# MicroMod-Teensy.net
KiCad netlist of a schematic drawn in EAGLE
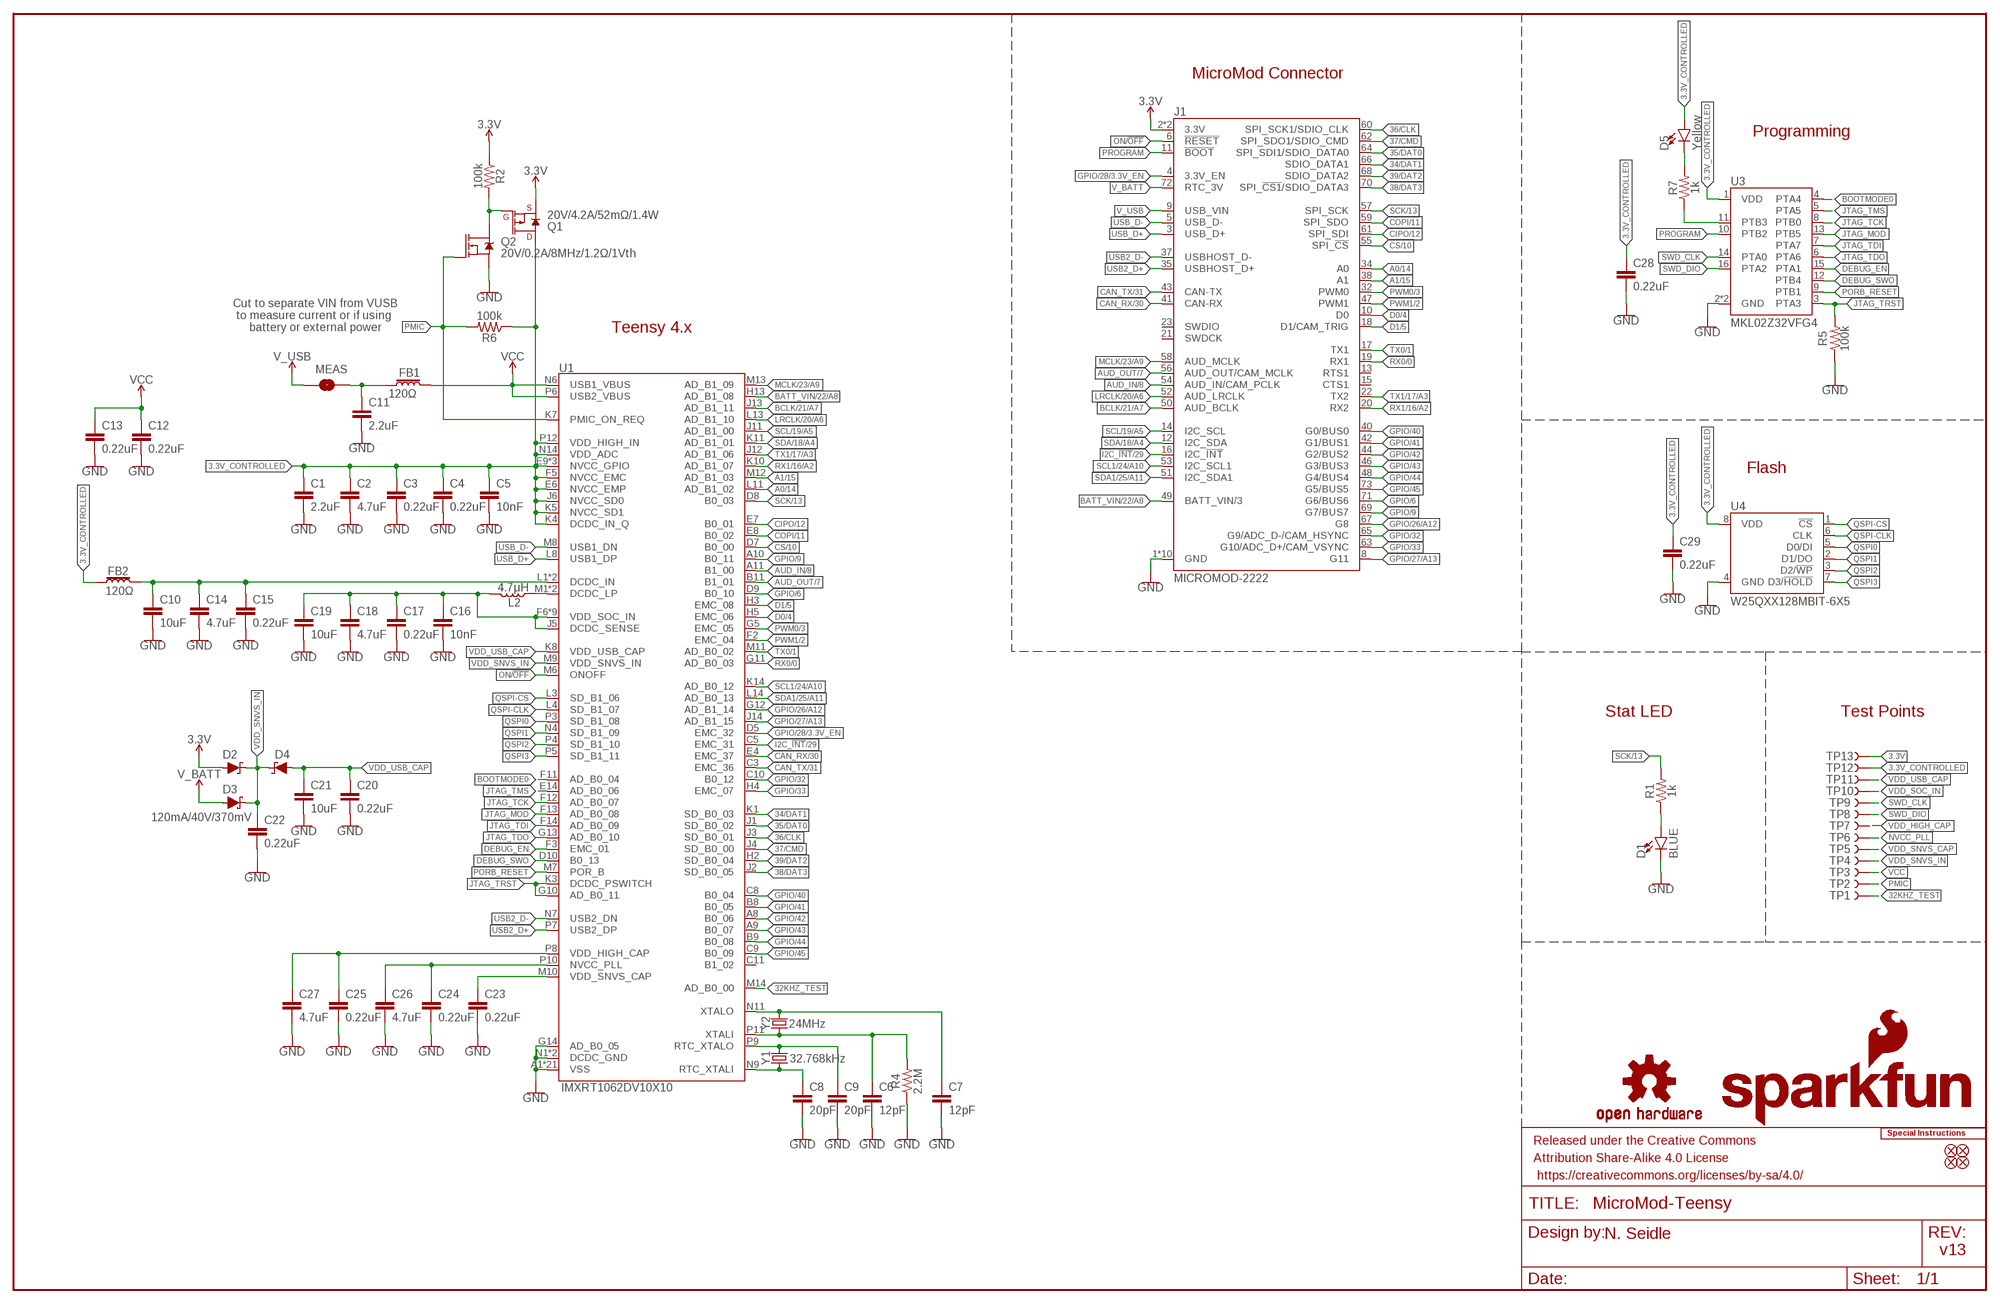
[diagram p0: schematic, sheet 1]

(export (version "E")
  (design (tool "Eeschema 10.0.6"))
  (components
    (comp (ref "C1")
      (value "2.2uF")
      (footprint "eagle-import:0402-TIGHT")
      (libsource (lib "eagle-import") (part "2.2UF-0402_TIGHT-10V-10%-X5R"))
    )
    (comp (ref "C2")
      (value "4.7uF")
      (footprint "eagle-import:0402-TIGHT")
      (libsource (lib "eagle-import") (part "4.7UF-0402_TIGHT-6.3V-20%-X5R"))
    )
    (comp (ref "C3")
      (value "0.22uF")
      (footprint "eagle-import:0402-TIGHT")
      (libsource (lib "eagle-import") (part "0.22UF-0402T-10V-10%"))
    )
    (comp (ref "C4")
      (value "0.22uF")
      (footprint "eagle-import:0402-TIGHT")
      (libsource (lib "eagle-import") (part "0.22UF-0402T-10V-10%"))
    )
    (comp (ref "C5")
      (value "10nF")
      (footprint "eagle-import:0402-TIGHT")
      (libsource (lib "eagle-import") (part "10NF-0402T-25V-10%"))
    )
    (comp (ref "C6")
      (value "12pF")
      (footprint "eagle-import:0402-TIGHT")
      (libsource (lib "eagle-import") (part "12PF-0402T-50V-5%"))
    )
    (comp (ref "C7")
      (value "12pF")
      (footprint "eagle-import:0402-TIGHT")
      (libsource (lib "eagle-import") (part "12PF-0402T-50V-5%"))
    )
    (comp (ref "C8")
      (value "20pF")
      (footprint "eagle-import:0402-TIGHT")
      (libsource (lib "eagle-import") (part "20PF-0402T-50V-5%"))
    )
    (comp (ref "C9")
      (value "20pF")
      (footprint "eagle-import:0402-TIGHT")
      (libsource (lib "eagle-import") (part "20PF-0402T-50V-5%"))
    )
    (comp (ref "C10")
      (value "10uF")
      (footprint "eagle-import:0402-TIGHT")
      (libsource (lib "eagle-import") (part "10UF-0402T-6.3V-20%"))
    )
    (comp (ref "C11")
      (value "2.2uF")
      (footprint "eagle-import:0402-TIGHT")
      (libsource (lib "eagle-import") (part "2.2UF-0402_TIGHT-10V-10%-X5R"))
    )
    (comp (ref "C12")
      (value "0.22uF")
      (footprint "eagle-import:0402-TIGHT")
      (libsource (lib "eagle-import") (part "0.22UF-0402T-10V-10%"))
    )
    (comp (ref "C13")
      (value "0.22uF")
      (footprint "eagle-import:0402-TIGHT")
      (libsource (lib "eagle-import") (part "0.22UF-0402T-10V-10%"))
    )
    (comp (ref "C14")
      (value "4.7uF")
      (footprint "eagle-import:0402-TIGHT")
      (libsource (lib "eagle-import") (part "4.7UF-0402_TIGHT-6.3V-20%-X5R"))
    )
    (comp (ref "C15")
      (value "0.22uF")
      (footprint "eagle-import:0402-TIGHT")
      (libsource (lib "eagle-import") (part "0.22UF-0402T-10V-10%"))
    )
    (comp (ref "C16")
      (value "10nF")
      (footprint "eagle-import:0402-TIGHT")
      (libsource (lib "eagle-import") (part "10NF-0402T-25V-10%"))
    )
    (comp (ref "C17")
      (value "0.22uF")
      (footprint "eagle-import:0402-TIGHT")
      (libsource (lib "eagle-import") (part "0.22UF-0402T-10V-10%"))
    )
    (comp (ref "C18")
      (value "4.7uF")
      (footprint "eagle-import:0402-TIGHT")
      (libsource (lib "eagle-import") (part "4.7UF-0402_TIGHT-6.3V-20%-X5R"))
    )
    (comp (ref "C19")
      (value "10uF")
      (footprint "eagle-import:0402-TIGHT")
      (libsource (lib "eagle-import") (part "10UF-0402T-6.3V-20%"))
    )
    (comp (ref "C20")
      (value "0.22uF")
      (footprint "eagle-import:0402-TIGHT")
      (libsource (lib "eagle-import") (part "0.22UF-0402T-10V-10%"))
    )
    (comp (ref "C21")
      (value "10uF")
      (footprint "eagle-import:0402-TIGHT")
      (libsource (lib "eagle-import") (part "10UF-0402T-6.3V-20%"))
    )
    (comp (ref "C22")
      (value "0.22uF")
      (footprint "eagle-import:0402-TIGHT")
      (libsource (lib "eagle-import") (part "0.22UF-0402T-10V-10%"))
    )
    (comp (ref "C23")
      (value "0.22uF")
      (footprint "eagle-import:0402-TIGHT")
      (libsource (lib "eagle-import") (part "0.22UF-0402T-10V-10%"))
    )
    (comp (ref "C24")
      (value "0.22uF")
      (footprint "eagle-import:0402-TIGHT")
      (libsource (lib "eagle-import") (part "0.22UF-0402T-10V-10%"))
    )
    (comp (ref "C25")
      (value "0.22uF")
      (footprint "eagle-import:0402-TIGHT")
      (libsource (lib "eagle-import") (part "0.22UF-0402T-10V-10%"))
    )
    (comp (ref "C26")
      (value "4.7uF")
      (footprint "eagle-import:0402-TIGHT")
      (libsource (lib "eagle-import") (part "4.7UF-0402_TIGHT-6.3V-20%-X5R"))
    )
    (comp (ref "C27")
      (value "4.7uF")
      (footprint "eagle-import:0402-TIGHT")
      (libsource (lib "eagle-import") (part "4.7UF-0402_TIGHT-6.3V-20%-X5R"))
    )
    (comp (ref "C28")
      (value "0.22uF")
      (footprint "eagle-import:0402-TIGHT")
      (libsource (lib "eagle-import") (part "0.22UF-0402T-10V-10%"))
    )
    (comp (ref "C29")
      (value "0.22uF")
      (footprint "eagle-import:0402-TIGHT")
      (libsource (lib "eagle-import") (part "0.22UF-0402T-10V-10%"))
    )
    (comp (ref "D1")
      (value "BLUE")
      (footprint "eagle-import:LED-0603")
      (libsource (lib "eagle-import") (part "LED-BLUE0603"))
    )
    (comp (ref "D2")
      (value "120mA/40V/370mV")
      (footprint "eagle-import:SOD-523")
      (libsource (lib "eagle-import") (part "DIODE-SCHOTTKY-RB751S40"))
    )
    (comp (ref "D3")
      (value "120mA/40V/370mV")
      (footprint "eagle-import:SOD-523")
      (libsource (lib "eagle-import") (part "DIODE-SCHOTTKY-RB751S40"))
    )
    (comp (ref "D4")
      (value "120mA/40V/370mV")
      (footprint "eagle-import:SOD-523")
      (libsource (lib "eagle-import") (part "DIODE-SCHOTTKY-RB751S40"))
    )
    (comp (ref "D5")
      (value "Yellow")
      (footprint "eagle-import:LED-0603")
      (libsource (lib "eagle-import") (part "LED-YELLOW0603"))
    )
    (comp (ref "FB1")
      (value "120Ω")
      (footprint "eagle-import:0402-TIGHT")
      (libsource (lib "eagle-import") (part "FERRITE_BEAD-120_OHM-0402T"))
    )
    (comp (ref "FB2")
      (value "120Ω")
      (footprint "eagle-import:0402-TIGHT")
      (libsource (lib "eagle-import") (part "FERRITE_BEAD-120_OHM-0402T"))
    )
    (comp (ref "FD1")
      (value "FIDUCIALUFIDUCIAL")
      (footprint "eagle-import:FIDUCIAL-MICRO")
      (libsource (lib "eagle-import") (part "FIDUCIALUFIDUCIAL"))
    )
    (comp (ref "FD2")
      (value "FIDUCIALUFIDUCIAL")
      (footprint "eagle-import:FIDUCIAL-MICRO")
      (libsource (lib "eagle-import") (part "FIDUCIALUFIDUCIAL"))
    )
    (comp (ref "FD3")
      (value "FIDUCIALUFIDUCIAL")
      (footprint "eagle-import:FIDUCIAL-MICRO")
      (libsource (lib "eagle-import") (part "FIDUCIALUFIDUCIAL"))
    )
    (comp (ref "FD4")
      (value "FIDUCIALUFIDUCIAL")
      (footprint "eagle-import:FIDUCIAL-MICRO")
      (libsource (lib "eagle-import") (part "FIDUCIALUFIDUCIAL"))
    )
    (comp (ref "FRAME1")
      (value "FRAME-LEDGER")
      (footprint "eagle-import:CREATIVE_COMMONS")
      (libsource (lib "eagle-import") (part "FRAME-LEDGER"))
    )
    (comp (ref "J1")
      (value "MICROMOD-2222")
      (footprint "eagle-import:M.2-CARD-E-22")
      (libsource (lib "eagle-import") (part "MICROMOD-2222"))
    )
    (comp (ref "L2")
      (value "4.7μH")
      (footprint "eagle-import:1008(2520)")
      (libsource (lib "eagle-import") (part "4.7μH_SHIELDED_INDUCTOR"))
    )
    (comp (ref "LOGO1")
      (value "SFE_LOGO_NAME_FLAME.1_INCH")
      (footprint "eagle-import:SFE_LOGO_NAME_FLAME_.1")
      (libsource (lib "eagle-import") (part "SFE_LOGO_NAME_FLAME.1_INCH"))
    )
    (comp (ref "LOGO2")
      (value "OSHW-LOGONO_SILK")
      (footprint "eagle-import:DUMMY")
      (libsource (lib "eagle-import") (part "OSHW-LOGONO_SILK"))
    )
    (comp (ref "LOGO3")
      (value "SPECIAL_INSTRUCTIONS-ORDERING")
      (footprint "eagle-import:ORDERING_INSTRUCTIONS")
      (libsource (lib "eagle-import") (part "SPECIAL_INSTRUCTIONS-ORDERING"))
    )
    (comp (ref "MEAS")
      (value "JUMPER-SMT_2_NC_TRACE_SILK")
      (footprint "eagle-import:SMT-JUMPER_2_NC_TRACE_SILK")
      (libsource (lib "eagle-import") (part "JUMPER-SMT_2_NC_TRACE_SILK"))
    )
    (comp (ref "Q1")
      (value "20V/4.2A/52mΩ/1.4W")
      (footprint "eagle-import:SOT23-3")
      (libsource (lib "eagle-import") (part "MOSFET_PCH-DMG2305UX-7"))
    )
    (comp (ref "Q2")
      (value "20V/0.2A/8MHz/1.2Ω/1Vth")
      (footprint "eagle-import:SOT-416FL")
      (libsource (lib "eagle-import") (part "MOSFET-NCH-RE1C00UNTL"))
    )
    (comp (ref "R1")
      (value "1k")
      (footprint "eagle-import:0402-TIGHT")
      (libsource (lib "eagle-import") (part "1KOHM-0402T-1/16W-1%"))
    )
    (comp (ref "R2")
      (value "100k")
      (footprint "eagle-import:0402-TIGHT")
      (libsource (lib "eagle-import") (part "100KOHM-0402T-1/16W-1%"))
    )
    (comp (ref "R4")
      (value "2.2M")
      (footprint "eagle-import:0402-TIGHT")
      (libsource (lib "eagle-import") (part "2.2MOHMS-0402T-1/10W-1%"))
    )
    (comp (ref "R5")
      (value "100k")
      (footprint "eagle-import:0402-TIGHT")
      (libsource (lib "eagle-import") (part "100KOHM-0402T-1/16W-1%"))
    )
    (comp (ref "R6")
      (value "100k")
      (footprint "eagle-import:0402-TIGHT")
      (libsource (lib "eagle-import") (part "100KOHM-0402T-1/16W-1%"))
    )
    (comp (ref "R7")
      (value "1k")
      (footprint "eagle-import:0402-TIGHT")
      (libsource (lib "eagle-import") (part "1KOHM-0402T-1/16W-1%"))
    )
    (comp (ref "TP1")
      (value "TEST-POINT3")
      (footprint "eagle-import:PAD.03X.03")
      (libsource (lib "eagle-import") (part "TEST-POINT3"))
    )
    (comp (ref "TP2")
      (value "TEST-POINT3")
      (footprint "eagle-import:PAD.03X.03")
      (libsource (lib "eagle-import") (part "TEST-POINT3"))
    )
    (comp (ref "TP3")
      (value "TEST-POINT3")
      (footprint "eagle-import:PAD.03X.03")
      (libsource (lib "eagle-import") (part "TEST-POINT3"))
    )
    (comp (ref "TP4")
      (value "TEST-POINT3")
      (footprint "eagle-import:PAD.03X.03")
      (libsource (lib "eagle-import") (part "TEST-POINT3"))
    )
    (comp (ref "TP5")
      (value "TEST-POINT3")
      (footprint "eagle-import:PAD.03X.03")
      (libsource (lib "eagle-import") (part "TEST-POINT3"))
    )
    (comp (ref "TP6")
      (value "TEST-POINT3")
      (footprint "eagle-import:PAD.03X.03")
      (libsource (lib "eagle-import") (part "TEST-POINT3"))
    )
    (comp (ref "TP7")
      (value "TEST-POINT3")
      (footprint "eagle-import:PAD.03X.03")
      (libsource (lib "eagle-import") (part "TEST-POINT3"))
    )
    (comp (ref "TP8")
      (value "TEST-POINT3")
      (footprint "eagle-import:PAD.03X.03")
      (libsource (lib "eagle-import") (part "TEST-POINT3"))
    )
    (comp (ref "TP9")
      (value "TEST-POINT3")
      (footprint "eagle-import:PAD.03X.03")
      (libsource (lib "eagle-import") (part "TEST-POINT3"))
    )
    (comp (ref "TP10")
      (value "TEST-POINT3")
      (footprint "eagle-import:PAD.03X.03")
      (libsource (lib "eagle-import") (part "TEST-POINT3"))
    )
    (comp (ref "TP11")
      (value "TEST-POINT3")
      (footprint "eagle-import:PAD.03X.03")
      (libsource (lib "eagle-import") (part "TEST-POINT3"))
    )
    (comp (ref "TP12")
      (value "TEST-POINT3")
      (footprint "eagle-import:PAD.03X.03")
      (libsource (lib "eagle-import") (part "TEST-POINT3"))
    )
    (comp (ref "TP13")
      (value "TEST-POINT3")
      (footprint "eagle-import:PAD.03X.03")
      (libsource (lib "eagle-import") (part "TEST-POINT3"))
    )
    (comp (ref "U1")
      (value "IMXRT1062DV10X10")
      (footprint "eagle-import:IMXRT1062")
      (libsource (lib "eagle-import") (part "IMXRT1062DV10X10"))
    )
    (comp (ref "U3")
      (value "MKL02Z32VFG4")
      (footprint "eagle-import:QFN-16")
      (libsource (lib "eagle-import") (part "MKL02Z32VFG4QFN-16"))
    )
    (comp (ref "U4")
      (value "W25QXX128MBIT-6X5")
      (footprint "eagle-import:WSON-8-6X5-SKINNY_CENTERPAD")
      (libsource (lib "eagle-import") (part "W25QXX128MBIT-6X5-SKINNY_CENTER"))
    )
    (comp (ref "Y1")
      (value "32.768kHz")
      (footprint "eagle-import:CRYSTAL-SMD-3.2X1.5MM")
      (libsource (lib "eagle-import") (part "CRYSTAL-32.768KHZSMD-3.2X1.5"))
    )
    (comp (ref "Y2")
      (value "24MHz")
      (footprint "eagle-import:CRYSTAL-SMD-2.0X1.6MM")
      (libsource (lib "eagle-import") (part "CRYSTAL-24MHZ-SMD-2.0X1.6MM"))
    )
  )
  (nets
    (net (code "1") (name "/I2C_~{INT}{slash}29") (class "Default")
      (node (ref "J1") (pin "16") (pinfunction "I2C_~{INT}_16") (pintype "bidirectional"))
      (node (ref "U1") (pin "C5") (pinfunction "EMC_31_C5") (pintype "bidirectional"))
    )
    (net (code "2") (name "/ON{slash}~{OFF}") (class "Default")
      (node (ref "J1") (pin "6") (pinfunction "~{RESET}_6") (pintype "bidirectional"))
      (node (ref "U1") (pin "M6") (pinfunction "ONOFF_M6") (pintype "bidirectional"))
    )
    (net (code "3") (name "3.3V") (class "Default")
      (node (ref "D2") (pin "A") (pinfunction "A_A") (pintype "passive"))
      (node (ref "J1") (pin "2") (pinfunction "3.3V_2") (pintype "bidirectional"))
      (node (ref "J1") (pin "74") (pinfunction "3.3V_74") (pintype "bidirectional"))
      (node (ref "Q1") (pin "2") (pinfunction "S_2") (pintype "bidirectional"))
      (node (ref "R2") (pin "1") (pinfunction "1_1") (pintype "passive"))
      (node (ref "TP13") (pin "P$1") (pinfunction "1_P$1") (pintype "bidirectional"))
    )
    (net (code "4") (name "3.3V_CONTROLLED") (class "Default")
      (node (ref "C1") (pin "1") (pinfunction "1_1") (pintype "passive"))
      (node (ref "C2") (pin "1") (pinfunction "1_1") (pintype "passive"))
      (node (ref "C28") (pin "1") (pinfunction "1_1") (pintype "passive"))
      (node (ref "C29") (pin "1") (pinfunction "1_1") (pintype "passive"))
      (node (ref "C3") (pin "1") (pinfunction "1_1") (pintype "passive"))
      (node (ref "C4") (pin "1") (pinfunction "1_1") (pintype "passive"))
      (node (ref "C5") (pin "1") (pinfunction "1_1") (pintype "passive"))
      (node (ref "D5") (pin "A") (pinfunction "A_A") (pintype "passive"))
      (node (ref "FB2") (pin "1") (pinfunction "1_1") (pintype "passive"))
      (node (ref "Q1") (pin "3") (pinfunction "D_3") (pintype "bidirectional"))
      (node (ref "R6") (pin "1") (pinfunction "1_1") (pintype "passive"))
      (node (ref "TP12") (pin "P$1") (pinfunction "1_P$1") (pintype "bidirectional"))
      (node (ref "U1") (pin "E6") (pinfunction "NVCC_EMP_E6") (pintype "bidirectional"))
      (node (ref "U1") (pin "E9") (pinfunction "NVCC_GPIO_E9") (pintype "bidirectional"))
      (node (ref "U1") (pin "F10") (pinfunction "NVCC_GPIO_F10") (pintype "bidirectional"))
      (node (ref "U1") (pin "F5") (pinfunction "NVCC_EMC_F5") (pintype "bidirectional"))
      (node (ref "U1") (pin "J10") (pinfunction "NVCC_GPIO_J10") (pintype "bidirectional"))
      (node (ref "U1") (pin "J6") (pinfunction "NVCC_SD0_J6") (pintype "bidirectional"))
      (node (ref "U1") (pin "K4") (pinfunction "DCDC_IN_Q_K4") (pintype "bidirectional"))
      (node (ref "U1") (pin "K5") (pinfunction "NVCC_SD1_K5") (pintype "bidirectional"))
      (node (ref "U1") (pin "N14") (pinfunction "VDD_ADC_N14") (pintype "bidirectional"))
      (node (ref "U1") (pin "P12") (pinfunction "VDD_HIGH_IN_P12") (pintype "bidirectional"))
      (node (ref "U3") (pin "1") (pinfunction "VDD_1") (pintype "bidirectional"))
      (node (ref "U4") (pin "8") (pinfunction "VDD_8") (pintype "bidirectional"))
    )
    (net (code "5") (name "32KHZ_TEST") (class "Default")
      (node (ref "TP1") (pin "P$1") (pinfunction "1_P$1") (pintype "bidirectional"))
      (node (ref "U1") (pin "M14") (pinfunction "AD_B0_00_M14") (pintype "bidirectional"))
    )
    (net (code "6") (name "34{slash}DAT1") (class "Default")
      (node (ref "J1") (pin "66") (pinfunction "SDIO_DATA1_66") (pintype "bidirectional"))
      (node (ref "U1") (pin "K1") (pinfunction "SD_B0_03_K1") (pintype "bidirectional"))
    )
    (net (code "7") (name "35{slash}DAT0") (class "Default")
      (node (ref "J1") (pin "64") (pinfunction "SPI_SDI1/SDIO_DATA0_64") (pintype "bidirectional"))
      (node (ref "U1") (pin "J1") (pinfunction "SD_B0_02_J1") (pintype "bidirectional"))
    )
    (net (code "8") (name "36{slash}CLK") (class "Default")
      (node (ref "J1") (pin "60") (pinfunction "SPI_SCK1/SDIO_CLK_60") (pintype "bidirectional"))
      (node (ref "U1") (pin "J3") (pinfunction "SD_B0_01_J3") (pintype "bidirectional"))
    )
    (net (code "9") (name "37{slash}CMD") (class "Default")
      (node (ref "J1") (pin "62") (pinfunction "SPI_SDO1/SDIO_CMD_62") (pintype "bidirectional"))
      (node (ref "U1") (pin "J4") (pinfunction "SD_B0_00_J4") (pintype "bidirectional"))
    )
    (net (code "10") (name "38{slash}DAT3") (class "Default")
      (node (ref "J1") (pin "70") (pinfunction "SPI_~{CS1}/SDIO_DATA3_70") (pintype "bidirectional"))
      (node (ref "U1") (pin "J2") (pinfunction "SD_B0_05_J2") (pintype "bidirectional"))
    )
    (net (code "11") (name "39{slash}DAT2") (class "Default")
      (node (ref "J1") (pin "68") (pinfunction "SDIO_DATA2_68") (pintype "bidirectional"))
      (node (ref "U1") (pin "H2") (pinfunction "SD_B0_04_H2") (pintype "bidirectional"))
    )
    (net (code "12") (name "A0{slash}14") (class "Default")
      (node (ref "J1") (pin "34") (pinfunction "A0_34") (pintype "bidirectional"))
      (node (ref "U1") (pin "L11") (pinfunction "AD_B1_02_L11") (pintype "bidirectional"))
    )
    (net (code "13") (name "A1{slash}15") (class "Default")
      (node (ref "J1") (pin "38") (pinfunction "A1_38") (pintype "bidirectional"))
      (node (ref "U1") (pin "M12") (pinfunction "AD_B1_03_M12") (pintype "bidirectional"))
    )
    (net (code "14") (name "AUD_IN{slash}8") (class "Default")
      (node (ref "J1") (pin "54") (pinfunction "AUD_IN/CAM_PCLK_54") (pintype "bidirectional"))
      (node (ref "U1") (pin "A11") (pinfunction "B1_00_A11") (pintype "bidirectional"))
    )
    (net (code "15") (name "AUD_OUT{slash}7") (class "Default")
      (node (ref "J1") (pin "56") (pinfunction "AUD_OUT/CAM_MCLK_56") (pintype "bidirectional"))
      (node (ref "U1") (pin "B11") (pinfunction "B1_01_B11") (pintype "bidirectional"))
    )
    (net (code "16") (name "BATT_VIN{slash}22{slash}A8") (class "Default")
      (node (ref "J1") (pin "49") (pinfunction "BATT_VIN/3_49") (pintype "bidirectional"))
      (node (ref "U1") (pin "H13") (pinfunction "AD_B1_08_H13") (pintype "bidirectional"))
    )
    (net (code "17") (name "BCLK{slash}21{slash}A7") (class "Default")
      (node (ref "J1") (pin "50") (pinfunction "AUD_BCLK_50") (pintype "bidirectional"))
      (node (ref "U1") (pin "J13") (pinfunction "AD_B1_11_J13") (pintype "bidirectional"))
    )
    (net (code "18") (name "BOOTMODE0") (class "Default")
      (node (ref "U1") (pin "F11") (pinfunction "AD_B0_04_F11") (pintype "bidirectional"))
      (node (ref "U3") (pin "4") (pinfunction "PTA4_4") (pintype "bidirectional"))
    )
    (net (code "19") (name "CAN_RX{slash}30") (class "Default")
      (node (ref "J1") (pin "41") (pinfunction "CAN-RX_41") (pintype "bidirectional"))
      (node (ref "U1") (pin "E4") (pinfunction "EMC_37_E4") (pintype "bidirectional"))
    )
    (net (code "20") (name "CAN_TX{slash}31") (class "Default")
      (node (ref "J1") (pin "43") (pinfunction "CAN-TX_43") (pintype "bidirectional"))
      (node (ref "U1") (pin "C3") (pinfunction "EMC_36_C3") (pintype "bidirectional"))
    )
    (net (code "21") (name "CIPO{slash}12") (class "Default")
      (node (ref "J1") (pin "61") (pinfunction "SPI_SDI_61") (pintype "bidirectional"))
      (node (ref "U1") (pin "E7") (pinfunction "B0_01_E7") (pintype "bidirectional"))
    )
    (net (code "22") (name "COPI{slash}11") (class "Default")
      (node (ref "J1") (pin "59") (pinfunction "SPI_SDO_59") (pintype "bidirectional"))
      (node (ref "U1") (pin "E8") (pinfunction "B0_02_E8") (pintype "bidirectional"))
    )
    (net (code "23") (name "CS{slash}10") (class "Default")
      (node (ref "J1") (pin "55") (pinfunction "SPI_~{CS}_55") (pintype "bidirectional"))
      (node (ref "U1") (pin "D7") (pinfunction "B0_00_D7") (pintype "bidirectional"))
    )
    (net (code "24") (name "D0{slash}4") (class "Default")
      (node (ref "J1") (pin "10") (pinfunction "D0_10") (pintype "bidirectional"))
      (node (ref "U1") (pin "H5") (pinfunction "EMC_06_H5") (pintype "bidirectional"))
    )
    (net (code "25") (name "D1{slash}5") (class "Default")
      (node (ref "J1") (pin "18") (pinfunction "D1/CAM_TRIG_18") (pintype "bidirectional"))
      (node (ref "U1") (pin "H3") (pinfunction "EMC_08_H3") (pintype "bidirectional"))
    )
    (net (code "26") (name "DEBUG_EN") (class "Default")
      (node (ref "U1") (pin "F3") (pinfunction "EMC_01_F3") (pintype "bidirectional"))
      (node (ref "U3") (pin "15") (pinfunction "PTA1_15") (pintype "bidirectional"))
    )
    (net (code "27") (name "DEBUG_SWO") (class "Default")
      (node (ref "U1") (pin "D10") (pinfunction "B0_13_D10") (pintype "bidirectional"))
      (node (ref "U3") (pin "12") (pinfunction "PTB4_12") (pintype "bidirectional"))
    )
    (net (code "28") (name "GND") (class "Default")
      (node (ref "C1") (pin "2") (pinfunction "2_2") (pintype "passive"))
      (node (ref "C10") (pin "2") (pinfunction "2_2") (pintype "passive"))
      (node (ref "C11") (pin "2") (pinfunction "2_2") (pintype "passive"))
      (node (ref "C12") (pin "2") (pinfunction "2_2") (pintype "passive"))
      (node (ref "C13") (pin "2") (pinfunction "2_2") (pintype "passive"))
      (node (ref "C14") (pin "2") (pinfunction "2_2") (pintype "passive"))
      (node (ref "C15") (pin "2") (pinfunction "2_2") (pintype "passive"))
      (node (ref "C16") (pin "2") (pinfunction "2_2") (pintype "passive"))
      (node (ref "C17") (pin "2") (pinfunction "2_2") (pintype "passive"))
      (node (ref "C18") (pin "2") (pinfunction "2_2") (pintype "passive"))
      (node (ref "C19") (pin "2") (pinfunction "2_2") (pintype "passive"))
      (node (ref "C2") (pin "2") (pinfunction "2_2") (pintype "passive"))
      (node (ref "C20") (pin "2") (pinfunction "2_2") (pintype "passive"))
      (node (ref "C21") (pin "2") (pinfunction "2_2") (pintype "passive"))
      (node (ref "C22") (pin "2") (pinfunction "2_2") (pintype "passive"))
      (node (ref "C23") (pin "2") (pinfunction "2_2") (pintype "passive"))
      (node (ref "C24") (pin "2") (pinfunction "2_2") (pintype "passive"))
      (node (ref "C25") (pin "2") (pinfunction "2_2") (pintype "passive"))
      (node (ref "C26") (pin "2") (pinfunction "2_2") (pintype "passive"))
      (node (ref "C27") (pin "2") (pinfunction "2_2") (pintype "passive"))
      (node (ref "C28") (pin "2") (pinfunction "2_2") (pintype "passive"))
      (node (ref "C29") (pin "2") (pinfunction "2_2") (pintype "passive"))
      (node (ref "C3") (pin "2") (pinfunction "2_2") (pintype "passive"))
      (node (ref "C4") (pin "2") (pinfunction "2_2") (pintype "passive"))
      (node (ref "C5") (pin "2") (pinfunction "2_2") (pintype "passive"))
      (node (ref "C6") (pin "2") (pinfunction "2_2") (pintype "passive"))
      (node (ref "C7") (pin "2") (pinfunction "2_2") (pintype "passive"))
      (node (ref "C8") (pin "2") (pinfunction "2_2") (pintype "passive"))
      (node (ref "C9") (pin "2") (pinfunction "2_2") (pintype "passive"))
      (node (ref "D1") (pin "C") (pinfunction "C_C") (pintype "passive"))
      (node (ref "J1") (pin "1") (pinfunction "GND_1") (pintype "bidirectional"))
      (node (ref "J1") (pin "33") (pinfunction "GND_33") (pintype "bidirectional"))
      (node (ref "J1") (pin "36") (pinfunction "GND_36") (pintype "bidirectional"))
      (node (ref "J1") (pin "39") (pinfunction "GND_39") (pintype "bidirectional"))
      (node (ref "J1") (pin "45") (pinfunction "GND_45") (pintype "bidirectional"))
      (node (ref "J1") (pin "7") (pinfunction "GND_7") (pintype "bidirectional"))
      (node (ref "J1") (pin "75") (pinfunction "GND_75") (pintype "bidirectional"))
      (node (ref "J1") (pin "GND1") (pinfunction "GND_GND1") (pintype "bidirectional"))
      (node (ref "J1") (pin "GND2") (pinfunction "GND_GND2") (pintype "bidirectional"))
      (node (ref "J1") (pin "GND3") (pinfunction "GND_GND3") (pintype "bidirectional"))
      (node (ref "Q2") (pin "2") (pinfunction "S_2") (pintype "bidirectional"))
      (node (ref "R4") (pin "1") (pinfunction "1_1") (pintype "passive"))
      (node (ref "R5") (pin "1") (pinfunction "1_1") (pintype "passive"))
      (node (ref "U1") (pin "A1") (pinfunction "VSS_A1") (pintype "bidirectional"))
      (node (ref "U1") (pin "A14") (pinfunction "VSS_A14") (pintype "bidirectional"))
      (node (ref "U1") (pin "B10") (pinfunction "VSS_B10") (pintype "bidirectional"))
      (node (ref "U1") (pin "B5") (pinfunction "VSS_B5") (pintype "bidirectional"))
      (node (ref "U1") (pin "E13") (pinfunction "VSS_E13") (pintype "bidirectional"))
      (node (ref "U1") (pin "E2") (pinfunction "VSS_E2") (pintype "bidirectional"))
      (node (ref "U1") (pin "G14") (pinfunction "AD_B0_05_G14") (pintype "bidirectional"))
      (node (ref "U1") (pin "G7") (pinfunction "VSS_G7") (pintype "bidirectional"))
      (node (ref "U1") (pin "G8") (pinfunction "VSS_G8") (pintype "bidirectional"))
      (node (ref "U1") (pin "H7") (pinfunction "VSS_H7") (pintype "bidirectional"))
      (node (ref "U1") (pin "H8") (pinfunction "VSS_H8") (pintype "bidirectional"))
      (node (ref "U1") (pin "J7") (pinfunction "VSS_J7") (pintype "bidirectional"))
      (node (ref "U1") (pin "J8") (pinfunction "VSS_J8") (pintype "bidirectional"))
      (node (ref "U1") (pin "K13") (pinfunction "VSS_K13") (pintype "bidirectional"))
      (node (ref "U1") (pin "K2") (pinfunction "VSS_K2") (pintype "bidirectional"))
      (node (ref "U1") (pin "K6") (pinfunction "VSS_K6") (pintype "bidirectional"))
      (node (ref "U1") (pin "K9") (pinfunction "VSS_K9") (pintype "bidirectional"))
      (node (ref "U1") (pin "L9") (pinfunction "VSS_L9") (pintype "bidirectional"))
      (node (ref "U1") (pin "N1") (pinfunction "DCDC_GND_N1") (pintype "bidirectional"))
      (node (ref "U1") (pin "N2") (pinfunction "DCDC_GND_N2") (pintype "bidirectional"))
      (node (ref "U1") (pin "N5") (pinfunction "VSS_N5") (pintype "bidirectional"))
      (node (ref "U1") (pin "N8") (pinfunction "VSS_N8") (pintype "bidirectional"))
      (node (ref "U1") (pin "P1") (pinfunction "VSS_P1") (pintype "bidirectional"))
      (node (ref "U1") (pin "P14") (pinfunction "VSS_P14") (pintype "bidirectional"))
      (node (ref "U3") (pin "17") (pinfunction "GND_17") (pintype "bidirectional"))
      (node (ref "U3") (pin "2") (pinfunction "GND_2") (pintype "bidirectional"))
      (node (ref "U4") (pin "4") (pinfunction "GND_4") (pintype "bidirectional"))
    )
    (net (code "29") (name "GPIO{slash}6") (class "Default")
      (node (ref "J1") (pin "71") (pinfunction "G6/BUS6_71") (pintype "bidirectional"))
      (node (ref "U1") (pin "D9") (pinfunction "B0_10_D9") (pintype "bidirectional"))
    )
    (net (code "30") (name "GPIO{slash}9") (class "Default")
      (node (ref "J1") (pin "69") (pinfunction "G7/BUS7_69") (pintype "bidirectional"))
      (node (ref "U1") (pin "A10") (pinfunction "B0_11_A10") (pintype "bidirectional"))
    )
    (net (code "31") (name "GPIO{slash}26{slash}A12") (class "Default")
      (node (ref "J1") (pin "67") (pinfunction "G8_67") (pintype "bidirectional"))
      (node (ref "U1") (pin "G12") (pinfunction "AD_B1_14_G12") (pintype "bidirectional"))
    )
    (net (code "32") (name "GPIO{slash}27{slash}A13") (class "Default")
      (node (ref "J1") (pin "8") (pinfunction "G11_8") (pintype "bidirectional"))
      (node (ref "U1") (pin "J14") (pinfunction "AD_B1_15_J14") (pintype "bidirectional"))
    )
    (net (code "33") (name "GPIO{slash}28{slash}3.3V_EN") (class "Default")
      (node (ref "J1") (pin "4") (pinfunction "3.3V_EN_4") (pintype "bidirectional"))
      (node (ref "U1") (pin "D5") (pinfunction "EMC_32_D5") (pintype "bidirectional"))
    )
    (net (code "34") (name "GPIO{slash}32") (class "Default")
      (node (ref "J1") (pin "65") (pinfunction "G9/ADC_D-/CAM_HSYNC_65") (pintype "bidirectional"))
      (node (ref "U1") (pin "C10") (pinfunction "B0_12_C10") (pintype "bidirectional"))
    )
    (net (code "35") (name "GPIO{slash}33") (class "Default")
      (node (ref "J1") (pin "63") (pinfunction "G10/ADC_D+/CAM_VSYNC_63") (pintype "bidirectional"))
      (node (ref "U1") (pin "H4") (pinfunction "EMC_07_H4") (pintype "bidirectional"))
    )
    (net (code "36") (name "GPIO{slash}40") (class "Default")
      (node (ref "J1") (pin "40") (pinfunction "G0/BUS0_40") (pintype "bidirectional"))
      (node (ref "U1") (pin "C8") (pinfunction "B0_04_C8") (pintype "bidirectional"))
    )
    (net (code "37") (name "GPIO{slash}41") (class "Default")
      (node (ref "J1") (pin "42") (pinfunction "G1/BUS1_42") (pintype "bidirectional"))
      (node (ref "U1") (pin "B8") (pinfunction "B0_05_B8") (pintype "bidirectional"))
    )
    (net (code "38") (name "GPIO{slash}42") (class "Default")
      (node (ref "J1") (pin "44") (pinfunction "G2/BUS2_44") (pintype "bidirectional"))
      (node (ref "U1") (pin "A8") (pinfunction "B0_06_A8") (pintype "bidirectional"))
    )
    (net (code "39") (name "GPIO{slash}43") (class "Default")
      (node (ref "J1") (pin "46") (pinfunction "G3/BUS3_46") (pintype "bidirectional"))
      (node (ref "U1") (pin "A9") (pinfunction "B0_07_A9") (pintype "bidirectional"))
    )
    (net (code "40") (name "GPIO{slash}44") (class "Default")
      (node (ref "J1") (pin "48") (pinfunction "G4/BUS4_48") (pintype "bidirectional"))
      (node (ref "U1") (pin "B9") (pinfunction "B0_08_B9") (pintype "bidirectional"))
    )
    (net (code "41") (name "GPIO{slash}45") (class "Default")
      (node (ref "J1") (pin "73") (pinfunction "G5/BUS5_73") (pintype "bidirectional"))
      (node (ref "U1") (pin "C9") (pinfunction "B0_09_C9") (pintype "bidirectional"))
    )
    (net (code "42") (name "JTAG_MOD") (class "Default")
      (node (ref "U1") (pin "F13") (pinfunction "AD_B0_08_F13") (pintype "bidirectional"))
      (node (ref "U3") (pin "13") (pinfunction "PTB5_13") (pintype "bidirectional"))
    )
    (net (code "43") (name "JTAG_TCK") (class "Default")
      (node (ref "U1") (pin "F12") (pinfunction "AD_B0_07_F12") (pintype "bidirectional"))
      (node (ref "U3") (pin "8") (pinfunction "PTB0_8") (pintype "bidirectional"))
    )
    (net (code "44") (name "JTAG_TDI") (class "Default")
      (node (ref "U1") (pin "F14") (pinfunction "AD_B0_09_F14") (pintype "bidirectional"))
      (node (ref "U3") (pin "7") (pinfunction "PTA7_7") (pintype "bidirectional"))
    )
    (net (code "45") (name "JTAG_TDO") (class "Default")
      (node (ref "U1") (pin "G13") (pinfunction "AD_B0_10_G13") (pintype "bidirectional"))
      (node (ref "U3") (pin "6") (pinfunction "PTA6_6") (pintype "bidirectional"))
    )
    (net (code "46") (name "JTAG_TMS") (class "Default")
      (node (ref "U1") (pin "E14") (pinfunction "AD_B0_06_E14") (pintype "bidirectional"))
      (node (ref "U3") (pin "5") (pinfunction "PTA5_5") (pintype "bidirectional"))
    )
    (net (code "47") (name "JTAG_TRST") (class "Default")
      (node (ref "R5") (pin "2") (pinfunction "2_2") (pintype "passive"))
      (node (ref "U1") (pin "G10") (pinfunction "AD_B0_11_G10") (pintype "bidirectional"))
      (node (ref "U1") (pin "K3") (pinfunction "DCDC_PSWITCH_K3") (pintype "bidirectional"))
      (node (ref "U3") (pin "3") (pinfunction "PTA3_3") (pintype "bidirectional"))
    )
    (net (code "48") (name "LRCLK{slash}20{slash}A6") (class "Default")
      (node (ref "J1") (pin "52") (pinfunction "AUD_LRCLK_52") (pintype "bidirectional"))
      (node (ref "U1") (pin "L13") (pinfunction "AD_B1_10_L13") (pintype "bidirectional"))
    )
    (net (code "49") (name "MCLK{slash}23{slash}A9") (class "Default")
      (node (ref "J1") (pin "58") (pinfunction "AUD_MCLK_58") (pintype "bidirectional"))
      (node (ref "U1") (pin "M13") (pinfunction "AD_B1_09_M13") (pintype "bidirectional"))
    )
    (net (code "50") (name "NVCC_PLL") (class "Default")
      (node (ref "C24") (pin "1") (pinfunction "1_1") (pintype "passive"))
      (node (ref "C26") (pin "1") (pinfunction "1_1") (pintype "passive"))
      (node (ref "TP6") (pin "P$1") (pinfunction "1_P$1") (pintype "bidirectional"))
      (node (ref "U1") (pin "P10") (pinfunction "NVCC_PLL_P10") (pintype "bidirectional"))
    )
    (net (code "51") (name "Net-(C10-Pad1)") (class "Default")
      (node (ref "C10") (pin "1") (pinfunction "1_1") (pintype "passive"))
      (node (ref "C14") (pin "1") (pinfunction "1_1") (pintype "passive"))
      (node (ref "C15") (pin "1") (pinfunction "1_1") (pintype "passive"))
      (node (ref "FB2") (pin "2") (pinfunction "2_2") (pintype "passive"))
      (node (ref "U1") (pin "L1") (pinfunction "DCDC_IN_L1") (pintype "bidirectional"))
      (node (ref "U1") (pin "L2") (pinfunction "DCDC_IN_L2") (pintype "bidirectional"))
    )
    (net (code "52") (name "Net-(C11-Pad1)") (class "Default")
      (node (ref "C11") (pin "1") (pinfunction "1_1") (pintype "passive"))
      (node (ref "FB1") (pin "1") (pinfunction "1_1") (pintype "passive"))
      (node (ref "MEAS") (pin "2") (pinfunction "2_2") (pintype "passive"))
    )
    (net (code "53") (name "Net-(D1-PadA)") (class "Default")
      (node (ref "D1") (pin "A") (pinfunction "A_A") (pintype "passive"))
      (node (ref "R1") (pin "1") (pinfunction "1_1") (pintype "passive"))
    )
    (net (code "54") (name "Net-(D5-PadC)") (class "Default")
      (node (ref "D5") (pin "C") (pinfunction "C_C") (pintype "passive"))
      (node (ref "R7") (pin "2") (pinfunction "2_2") (pintype "passive"))
    )
    (net (code "55") (name "Net-(L2-Pad1)") (class "Default")
      (node (ref "L2") (pin "1") (pinfunction "1_1") (pintype "passive"))
      (node (ref "U1") (pin "M1") (pinfunction "DCDC_LP_M1") (pintype "bidirectional"))
      (node (ref "U1") (pin "M2") (pinfunction "DCDC_LP_M2") (pintype "bidirectional"))
    )
    (net (code "56") (name "Net-(Q1-G)") (class "Default")
      (node (ref "Q1") (pin "1") (pinfunction "G_1") (pintype "bidirectional"))
      (node (ref "Q2") (pin "3") (pinfunction "D_3") (pintype "bidirectional"))
      (node (ref "R2") (pin "2") (pinfunction "2_2") (pintype "passive"))
    )
    (net (code "57") (name "Net-(U1-RTC_XTALI)") (class "Default")
      (node (ref "C8") (pin "1") (pinfunction "1_1") (pintype "passive"))
      (node (ref "U1") (pin "N9") (pinfunction "RTC_XTALI_N9") (pintype "bidirectional"))
      (node (ref "Y1") (pin "P$1") (pinfunction "1_P$1") (pintype "passive"))
    )
    (net (code "58") (name "Net-(U1-RTC_XTALO)") (class "Default")
      (node (ref "C9") (pin "1") (pinfunction "1_1") (pintype "passive"))
      (node (ref "U1") (pin "P9") (pinfunction "RTC_XTALO_P9") (pintype "bidirectional"))
      (node (ref "Y1") (pin "P$2") (pinfunction "2_P$2") (pintype "passive"))
    )
    (net (code "59") (name "Net-(U1-XTALI)") (class "Default")
      (node (ref "C6") (pin "1") (pinfunction "1_1") (pintype "passive"))
      (node (ref "R4") (pin "2") (pinfunction "2_2") (pintype "passive"))
      (node (ref "U1") (pin "P11") (pinfunction "XTALI_P11") (pintype "bidirectional"))
      (node (ref "Y2") (pin "1") (pinfunction "1_1") (pintype "passive"))
    )
    (net (code "60") (name "Net-(U1-XTALO)") (class "Default")
      (node (ref "C7") (pin "1") (pinfunction "1_1") (pintype "passive"))
      (node (ref "U1") (pin "N11") (pinfunction "XTALO_N11") (pintype "bidirectional"))
      (node (ref "Y2") (pin "3") (pinfunction "2_3") (pintype "passive"))
    )
    (net (code "61") (name "Net-(U3-PTB3)") (class "Default")
      (node (ref "R7") (pin "1") (pinfunction "1_1") (pintype "passive"))
      (node (ref "U3") (pin "11") (pinfunction "PTB3_11") (pintype "bidirectional"))
    )
    (net (code "62") (name "PMIC") (class "Default")
      (node (ref "Q2") (pin "1") (pinfunction "G_1") (pintype "bidirectional"))
      (node (ref "R6") (pin "2") (pinfunction "2_2") (pintype "passive"))
      (node (ref "TP2") (pin "P$1") (pinfunction "1_P$1") (pintype "bidirectional"))
      (node (ref "U1") (pin "K7") (pinfunction "PMIC_ON_REQ_K7") (pintype "bidirectional"))
    )
    (net (code "63") (name "PORB_RESET") (class "Default")
      (node (ref "U1") (pin "M7") (pinfunction "POR_B_M7") (pintype "bidirectional"))
      (node (ref "U3") (pin "9") (pinfunction "PTB1_9") (pintype "bidirectional"))
    )
    (net (code "64") (name "PROGRAM") (class "Default")
      (node (ref "J1") (pin "11") (pinfunction "~{BOOT}_11") (pintype "bidirectional"))
      (node (ref "U3") (pin "10") (pinfunction "PTB2_10") (pintype "bidirectional"))
    )
    (net (code "65") (name "PWM0{slash}3") (class "Default")
      (node (ref "J1") (pin "32") (pinfunction "PWM0_32") (pintype "bidirectional"))
      (node (ref "U1") (pin "G5") (pinfunction "EMC_05_G5") (pintype "bidirectional"))
    )
    (net (code "66") (name "PWM1{slash}2") (class "Default")
      (node (ref "J1") (pin "47") (pinfunction "PWM1_47") (pintype "bidirectional"))
      (node (ref "U1") (pin "F2") (pinfunction "EMC_04_F2") (pintype "bidirectional"))
    )
    (net (code "67") (name "QSPI-CLK") (class "Default")
      (node (ref "U1") (pin "L4") (pinfunction "SD_B1_07_L4") (pintype "bidirectional"))
      (node (ref "U4") (pin "6") (pinfunction "CLK_6") (pintype "bidirectional"))
    )
    (net (code "68") (name "QSPI-CS") (class "Default")
      (node (ref "U1") (pin "L3") (pinfunction "SD_B1_06_L3") (pintype "bidirectional"))
      (node (ref "U4") (pin "1") (pinfunction "~{CS}_1") (pintype "bidirectional"))
    )
    (net (code "69") (name "QSPI0") (class "Default")
      (node (ref "U1") (pin "P3") (pinfunction "SD_B1_08_P3") (pintype "bidirectional"))
      (node (ref "U4") (pin "5") (pinfunction "D0/DI_5") (pintype "bidirectional"))
    )
    (net (code "70") (name "QSPI1") (class "Default")
      (node (ref "U1") (pin "N4") (pinfunction "SD_B1_09_N4") (pintype "bidirectional"))
      (node (ref "U4") (pin "2") (pinfunction "D1/DO_2") (pintype "bidirectional"))
    )
    (net (code "71") (name "QSPI2") (class "Default")
      (node (ref "U1") (pin "P4") (pinfunction "SD_B1_10_P4") (pintype "bidirectional"))
      (node (ref "U4") (pin "3") (pinfunction "D2/~{WP}_3") (pintype "bidirectional"))
    )
    (net (code "72") (name "QSPI3") (class "Default")
      (node (ref "U1") (pin "P5") (pinfunction "SD_B1_11_P5") (pintype "bidirectional"))
      (node (ref "U4") (pin "7") (pinfunction "D3/~{HOLD}_7") (pintype "bidirectional"))
    )
    (net (code "73") (name "RX0{slash}0") (class "Default")
      (node (ref "J1") (pin "19") (pinfunction "RX1_19") (pintype "bidirectional"))
      (node (ref "U1") (pin "G11") (pinfunction "AD_B0_03_G11") (pintype "bidirectional"))
    )
    (net (code "74") (name "RX1{slash}16{slash}A2") (class "Default")
      (node (ref "J1") (pin "20") (pinfunction "RX2_20") (pintype "bidirectional"))
      (node (ref "U1") (pin "K10") (pinfunction "AD_B1_07_K10") (pintype "bidirectional"))
    )
    (net (code "75") (name "SCK{slash}13") (class "Default")
      (node (ref "J1") (pin "57") (pinfunction "SPI_SCK_57") (pintype "bidirectional"))
      (node (ref "R1") (pin "2") (pinfunction "2_2") (pintype "passive"))
      (node (ref "U1") (pin "D8") (pinfunction "B0_03_D8") (pintype "bidirectional"))
    )
    (net (code "76") (name "SCL1{slash}24{slash}A10") (class "Default")
      (node (ref "J1") (pin "53") (pinfunction "I2C_SCL1_53") (pintype "bidirectional"))
      (node (ref "U1") (pin "K14") (pinfunction "AD_B0_12_K14") (pintype "bidirectional"))
    )
    (net (code "77") (name "SCL{slash}19{slash}A5") (class "Default")
      (node (ref "J1") (pin "14") (pinfunction "I2C_SCL_14") (pintype "bidirectional"))
      (node (ref "U1") (pin "J11") (pinfunction "AD_B1_00_J11") (pintype "bidirectional"))
    )
    (net (code "78") (name "SDA1{slash}25{slash}A11") (class "Default")
      (node (ref "J1") (pin "51") (pinfunction "I2C_SDA1_51") (pintype "bidirectional"))
      (node (ref "U1") (pin "L14") (pinfunction "AD_B0_13_L14") (pintype "bidirectional"))
    )
    (net (code "79") (name "SDA{slash}18{slash}A4") (class "Default")
      (node (ref "J1") (pin "12") (pinfunction "I2C_SDA_12") (pintype "bidirectional"))
      (node (ref "U1") (pin "K11") (pinfunction "AD_B1_01_K11") (pintype "bidirectional"))
    )
    (net (code "80") (name "SWD_CLK") (class "Default")
      (node (ref "TP9") (pin "P$1") (pinfunction "1_P$1") (pintype "bidirectional"))
      (node (ref "U3") (pin "14") (pinfunction "PTA0_14") (pintype "bidirectional"))
    )
    (net (code "81") (name "SWD_DIO") (class "Default")
      (node (ref "TP8") (pin "P$1") (pinfunction "1_P$1") (pintype "bidirectional"))
      (node (ref "U3") (pin "16") (pinfunction "PTA2_16") (pintype "bidirectional"))
    )
    (net (code "82") (name "TX0{slash}1") (class "Default")
      (node (ref "J1") (pin "17") (pinfunction "TX1_17") (pintype "bidirectional"))
      (node (ref "U1") (pin "M11") (pinfunction "AD_B0_02_M11") (pintype "bidirectional"))
    )
    (net (code "83") (name "TX1{slash}17{slash}A3") (class "Default")
      (node (ref "J1") (pin "22") (pinfunction "TX2_22") (pintype "bidirectional"))
      (node (ref "U1") (pin "J12") (pinfunction "AD_B1_06_J12") (pintype "bidirectional"))
    )
    (net (code "84") (name "USB2_D+") (class "Default")
      (node (ref "J1") (pin "35") (pinfunction "USBHOST_D+_35") (pintype "bidirectional"))
      (node (ref "U1") (pin "P7") (pinfunction "USB2_DP_P7") (pintype "bidirectional"))
    )
    (net (code "85") (name "USB2_D-") (class "Default")
      (node (ref "J1") (pin "37") (pinfunction "USBHOST_D-_37") (pintype "bidirectional"))
      (node (ref "U1") (pin "N7") (pinfunction "USB2_DN_N7") (pintype "bidirectional"))
    )
    (net (code "86") (name "USB_D+") (class "Default")
      (node (ref "J1") (pin "3") (pinfunction "USB_D+_3") (pintype "bidirectional"))
      (node (ref "U1") (pin "L8") (pinfunction "USB1_DP_L8") (pintype "bidirectional"))
    )
    (net (code "87") (name "USB_D-") (class "Default")
      (node (ref "J1") (pin "5") (pinfunction "USB_D-_5") (pintype "bidirectional"))
      (node (ref "U1") (pin "M8") (pinfunction "USB1_DN_M8") (pintype "bidirectional"))
    )
    (net (code "88") (name "VCC") (class "Default")
      (node (ref "C12") (pin "1") (pinfunction "1_1") (pintype "passive"))
      (node (ref "C13") (pin "1") (pinfunction "1_1") (pintype "passive"))
      (node (ref "FB1") (pin "2") (pinfunction "2_2") (pintype "passive"))
      (node (ref "TP3") (pin "P$1") (pinfunction "1_P$1") (pintype "bidirectional"))
      (node (ref "U1") (pin "N6") (pinfunction "USB1_VBUS_N6") (pintype "bidirectional"))
      (node (ref "U1") (pin "P6") (pinfunction "USB2_VBUS_P6") (pintype "bidirectional"))
    )
    (net (code "89") (name "VDD_HIGH_CAP") (class "Default")
      (node (ref "C25") (pin "1") (pinfunction "1_1") (pintype "passive"))
      (node (ref "C27") (pin "1") (pinfunction "1_1") (pintype "passive"))
      (node (ref "TP7") (pin "P$1") (pinfunction "1_P$1") (pintype "bidirectional"))
      (node (ref "U1") (pin "P8") (pinfunction "VDD_HIGH_CAP_P8") (pintype "bidirectional"))
    )
    (net (code "90") (name "VDD_SNVS_CAP") (class "Default")
      (node (ref "C23") (pin "1") (pinfunction "1_1") (pintype "passive"))
      (node (ref "TP5") (pin "P$1") (pinfunction "1_P$1") (pintype "bidirectional"))
      (node (ref "U1") (pin "M10") (pinfunction "VDD_SNVS_CAP_M10") (pintype "bidirectional"))
    )
    (net (code "91") (name "VDD_SNVS_IN") (class "Default")
      (node (ref "C22") (pin "1") (pinfunction "1_1") (pintype "passive"))
      (node (ref "D2") (pin "C") (pinfunction "C_C") (pintype "passive"))
      (node (ref "D3") (pin "C") (pinfunction "C_C") (pintype "passive"))
      (node (ref "D4") (pin "C") (pinfunction "C_C") (pintype "passive"))
      (node (ref "TP4") (pin "P$1") (pinfunction "1_P$1") (pintype "bidirectional"))
      (node (ref "U1") (pin "M9") (pinfunction "VDD_SNVS_IN_M9") (pintype "bidirectional"))
    )
    (net (code "92") (name "VDD_SOC_IN") (class "Default")
      (node (ref "C16") (pin "1") (pinfunction "1_1") (pintype "passive"))
      (node (ref "C17") (pin "1") (pinfunction "1_1") (pintype "passive"))
      (node (ref "C18") (pin "1") (pinfunction "1_1") (pintype "passive"))
      (node (ref "C19") (pin "1") (pinfunction "1_1") (pintype "passive"))
      (node (ref "L2") (pin "2") (pinfunction "2_2") (pintype "passive"))
      (node (ref "TP10") (pin "P$1") (pinfunction "1_P$1") (pintype "bidirectional"))
      (node (ref "U1") (pin "F6") (pinfunction "VDD_SOC_IN_F6") (pintype "bidirectional"))
      (node (ref "U1") (pin "F7") (pinfunction "VDD_SOC_IN_F7") (pintype "bidirectional"))
      (node (ref "U1") (pin "F8") (pinfunction "VDD_SOC_IN_F8") (pintype "bidirectional"))
      (node (ref "U1") (pin "F9") (pinfunction "VDD_SOC_IN_F9") (pintype "bidirectional"))
      (node (ref "U1") (pin "G6") (pinfunction "VDD_SOC_IN_G6") (pintype "bidirectional"))
      (node (ref "U1") (pin "G9") (pinfunction "VDD_SOC_IN_G9") (pintype "bidirectional"))
      (node (ref "U1") (pin "H6") (pinfunction "VDD_SOC_IN_H6") (pintype "bidirectional"))
      (node (ref "U1") (pin "H9") (pinfunction "VDD_SOC_IN_H9") (pintype "bidirectional"))
      (node (ref "U1") (pin "J5") (pinfunction "DCDC_SENSE_J5") (pintype "bidirectional"))
      (node (ref "U1") (pin "J9") (pinfunction "VDD_SOC_IN_J9") (pintype "bidirectional"))
    )
    (net (code "93") (name "VDD_USB_CAP") (class "Default")
      (node (ref "C20") (pin "1") (pinfunction "1_1") (pintype "passive"))
      (node (ref "C21") (pin "1") (pinfunction "1_1") (pintype "passive"))
      (node (ref "D4") (pin "A") (pinfunction "A_A") (pintype "passive"))
      (node (ref "TP11") (pin "P$1") (pinfunction "1_P$1") (pintype "bidirectional"))
      (node (ref "U1") (pin "K8") (pinfunction "VDD_USB_CAP_K8") (pintype "bidirectional"))
    )
    (net (code "94") (name "V_BATT") (class "Default")
      (node (ref "D3") (pin "A") (pinfunction "A_A") (pintype "passive"))
      (node (ref "J1") (pin "72") (pinfunction "RTC_3V_72") (pintype "bidirectional"))
    )
    (net (code "95") (name "V_USB") (class "Default")
      (node (ref "J1") (pin "9") (pinfunction "USB_VIN_9") (pintype "bidirectional"))
      (node (ref "MEAS") (pin "1") (pinfunction "1_1") (pintype "passive"))
    )
    (net (code "96") (name "unconnected-(J1-CTS1-Pad15)") (class "Default")
      (node (ref "J1") (pin "15") (pinfunction "CTS1_15") (pintype "bidirectional"))
    )
    (net (code "97") (name "unconnected-(J1-RTS1-Pad13)") (class "Default")
      (node (ref "J1") (pin "13") (pinfunction "RTS1_13") (pintype "bidirectional"))
    )
    (net (code "98") (name "unconnected-(J1-SWDCK-Pad21)") (class "Default")
      (node (ref "J1") (pin "21") (pinfunction "SWDCK_21") (pintype "bidirectional"))
    )
    (net (code "99") (name "unconnected-(J1-SWDIO-Pad23)") (class "Default")
      (node (ref "J1") (pin "23") (pinfunction "SWDIO_23") (pintype "bidirectional"))
    )
    (net (code "100") (name "unconnected-(U1-B1_02-PadC11)") (class "Default")
      (node (ref "U1") (pin "C11") (pinfunction "B1_02_C11") (pintype "bidirectional"))
    )
  )
)
